# DIn_Isolator.net
KiCad netlist of a schematic drawn in Altium Designer
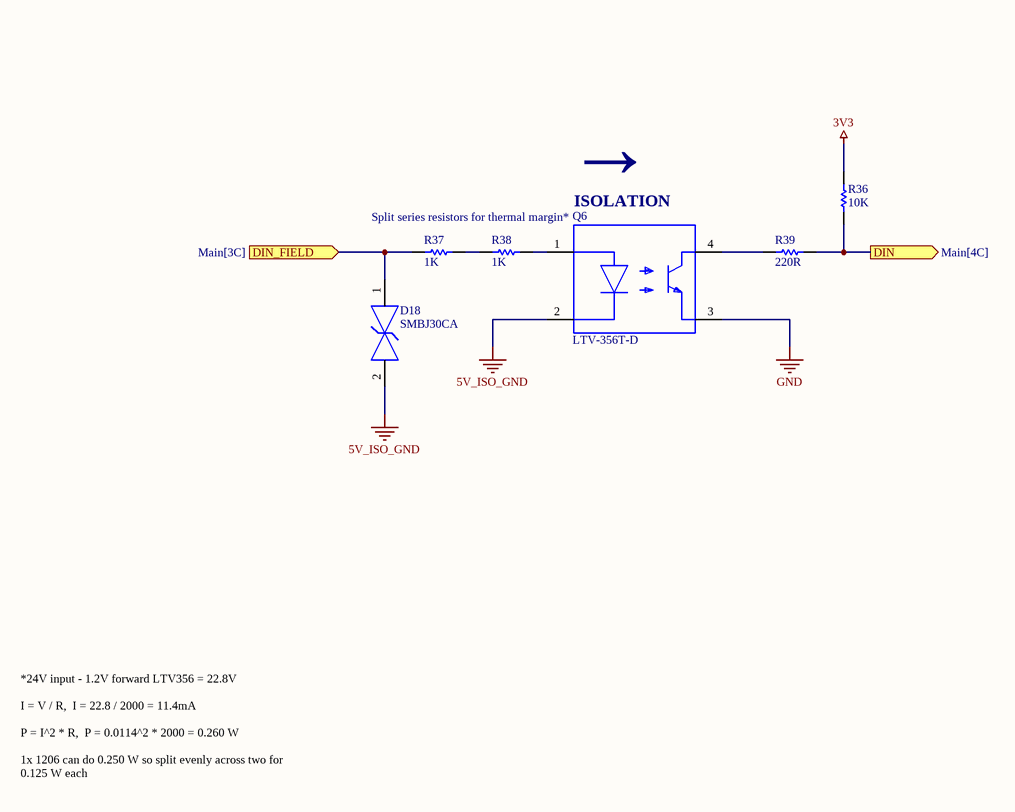
[diagram p0: DIn_Isolator.SchDoc]

(export (version "E")
  (design (tool "Eeschema 10.0.6"))
  (components
    (comp (ref "D18")
      (value "SMBJ30CA")
      (footprint "FP-SMBJ30CAHE3-52-MFG")
      (description "TVS DIODE 30V 48.4V DO214AA")
      (fields
        (field (name "OCTOPART") "https://octopart.com/smbj30cahe3%2F52-vishay-43725255")
        (field (name "MANUFACTURER") "Vishay Semiconductor Diodes Division")
      )
      (libsource (lib "Altium Content Vault") (part "876f4347bf90aa6f500f43e3cd03972"))
    )
    (comp (ref "Q6")
      (value "LTV-356T-D")
      (footprint "FP-LTV-356T-D-MFG")
      (description "OPTOCPL 1 CH TRAN OUT SMT")
      (fields
        (field (name "MANUFACTURER") "Lite-On")
        (field (name "OCTOPART") "https://octopart.com/ltv-356t-d-lite-on-11764243")
      )
      (libsource (lib "Altium Content Vault") (part "34aec040319b23b6d7df8c049769266"))
    )
    (comp (ref "R36")
      (value "10K")
      (footprint "RESC1609X55X30LL15T15")
      (description "Chip Resistor, 10 KOhm, +/- 1%, 0.1 W, -55 to 155 degC, 0603 (1608 Metric), RoHS, Tape and Reel")
      (fields (field (name "TOLERANCE") "1%") (field (name "MANUFACTURER") "Panasonic"))
      (libsource (lib "Altium Content Vault") (part "RES-2"))
    )
    (comp (ref "R37")
      (value "1K")
      (footprint "RESC3216X70X50ML20T25")
      (fields (field (name "PART NUMBER") "ERA8AEB102V") (field (name "MANUFACTURER") "Panasonic"))
      (libsource (lib "Altium Content Vault") (part "RES"))
    )
    (comp (ref "R38")
      (value "1K")
      (footprint "RESC3216X70X50ML20T25")
      (fields (field (name "PART NUMBER") "ERA8AEB102V") (field (name "MANUFACTURER") "Panasonic"))
      (libsource (lib "Altium Content Vault") (part "RES"))
    )
    (comp (ref "R39")
      (value "220R")
      (footprint "RESC1608X55X30LL15T15")
      (description "Chip Resistor, 220 Ohm, +/- 1%, 0.1 W, -55 to 155 degC, 0603 (1608 Metric), RoHS, Tape and Reel")
      (fields (field (name "TOLERANCE") "1%"))
      (libsource (lib "Altium Content Vault") (part "RES-2"))
    )
  )
  (nets
    (net (code "1") (name "/DIN") (class "Default")
      (node (ref "R36") (pin "2") (pinfunction "2_2") (pintype "passive"))
      (node (ref "R39") (pin "2") (pinfunction "2_2") (pintype "passive"))
    )
    (net (code "2") (name "/DIN_FIELD") (class "Default")
      (node (ref "D18") (pin "1") (pinfunction "1_1") (pintype "passive"))
      (node (ref "R37") (pin "1") (pinfunction "1_1") (pintype "passive"))
    )
    (net (code "3") (name "3V3") (class "Default")
      (node (ref "R36") (pin "1") (pinfunction "1_1") (pintype "passive"))
    )
    (net (code "4") (name "5V_ISO_GND") (class "Default")
      (node (ref "D18") (pin "2") (pinfunction "2_2") (pintype "passive"))
      (node (ref "Q6") (pin "2") (pinfunction "C_2") (pintype "passive"))
    )
    (net (code "5") (name "GND") (class "Default")
      (node (ref "Q6") (pin "3") (pinfunction "E_3") (pintype "passive"))
    )
    (net (code "6") (name "Net-(Q6-A)") (class "Default")
      (node (ref "Q6") (pin "1") (pinfunction "A_1") (pintype "passive"))
      (node (ref "R38") (pin "2") (pinfunction "2_2") (pintype "passive"))
    )
    (net (code "7") (name "Net-(Q6-C-Pad4)") (class "Default")
      (node (ref "Q6") (pin "4") (pinfunction "C_4") (pintype "passive"))
      (node (ref "R39") (pin "1") (pinfunction "1_1") (pintype "passive"))
    )
    (net (code "8") (name "Net-(R37-Pad2)") (class "Default")
      (node (ref "R37") (pin "2") (pinfunction "2_2") (pintype "passive"))
      (node (ref "R38") (pin "1") (pinfunction "1_1") (pintype "passive"))
    )
  )
)
